# Infinity_Mirror_005.net
KiCad netlist of a schematic drawn in EAGLE
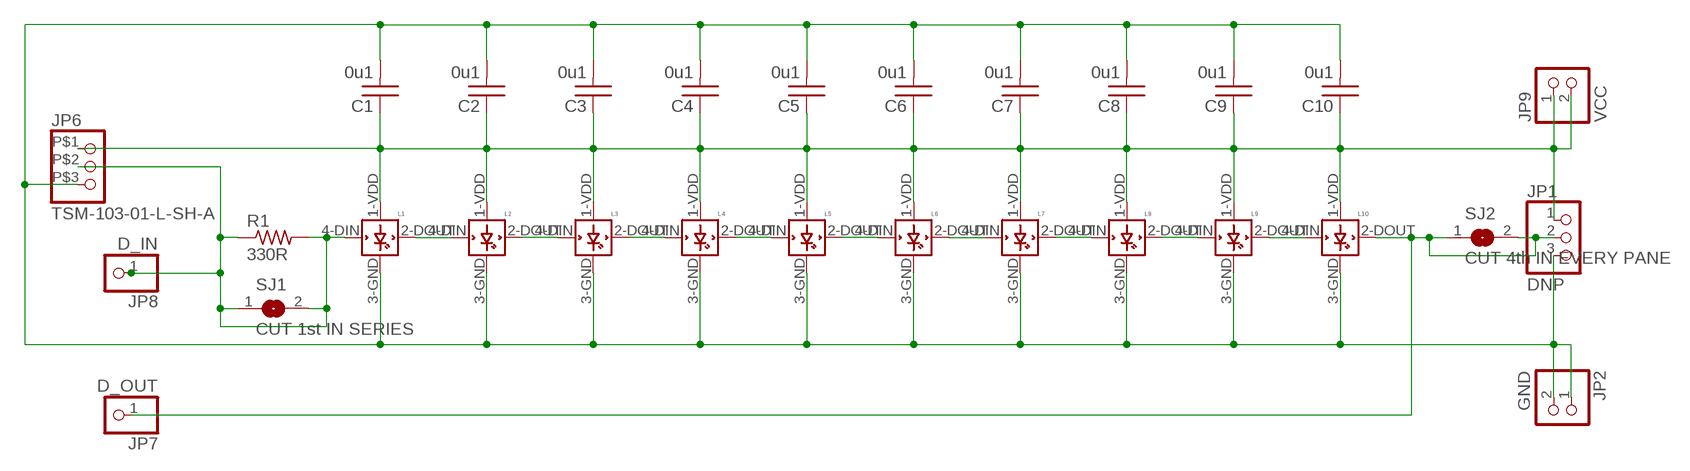
[diagram p0: schematic, sheet 1]

(export (version "E")
  (design (tool "Eeschema 10.0.6"))
  (components
    (comp (ref "C1")
      (value "0u1")
      (footprint "eagle-import:C1206")
      (libsource (lib "eagle-import") (part "C-USC1206"))
    )
    (comp (ref "C2")
      (value "0u1")
      (footprint "eagle-import:C1206")
      (libsource (lib "eagle-import") (part "C-USC1206"))
    )
    (comp (ref "C3")
      (value "0u1")
      (footprint "eagle-import:C1206")
      (libsource (lib "eagle-import") (part "C-USC1206"))
    )
    (comp (ref "C4")
      (value "0u1")
      (footprint "eagle-import:C1206")
      (libsource (lib "eagle-import") (part "C-USC1206"))
    )
    (comp (ref "C5")
      (value "0u1")
      (footprint "eagle-import:C1206")
      (libsource (lib "eagle-import") (part "C-USC1206"))
    )
    (comp (ref "C6")
      (value "0u1")
      (footprint "eagle-import:C1206")
      (libsource (lib "eagle-import") (part "C-USC1206"))
    )
    (comp (ref "C7")
      (value "0u1")
      (footprint "eagle-import:C1206")
      (libsource (lib "eagle-import") (part "C-USC1206"))
    )
    (comp (ref "C8")
      (value "0u1")
      (footprint "eagle-import:C1206")
      (libsource (lib "eagle-import") (part "C-USC1206"))
    )
    (comp (ref "C9")
      (value "0u1")
      (footprint "eagle-import:C1206")
      (libsource (lib "eagle-import") (part "C-USC1206"))
    )
    (comp (ref "C10")
      (value "0u1")
      (footprint "eagle-import:C1206")
      (libsource (lib "eagle-import") (part "C-USC1206"))
    )
    (comp (ref "JP1")
      (value "DNP")
      (footprint "eagle-import:1X03-CLEANBIG")
      (libsource (lib "eagle-import") (part "PINHD-1X3CB"))
    )
    (comp (ref "JP2")
      (value "GND")
      (footprint "eagle-import:1X02-CLEANBIG")
      (libsource (lib "eagle-import") (part "PINHD-1X2"))
    )
    (comp (ref "JP6")
      (value "TSM-103-01-L-SH-A")
      (footprint "eagle-import:TSM-103-01-L-SH-A")
      (libsource (lib "eagle-import") (part "TSM-103-01-L-SH-A"))
    )
    (comp (ref "JP7")
      (value "D_OUT")
      (footprint "eagle-import:1X01-CLEANBIG")
      (libsource (lib "eagle-import") (part "PINHD-1X1CB"))
    )
    (comp (ref "JP8")
      (value "D_IN")
      (footprint "eagle-import:1X01-CLEANBIG")
      (libsource (lib "eagle-import") (part "PINHD-1X1CB"))
    )
    (comp (ref "JP9")
      (value "VCC")
      (footprint "eagle-import:1X02-CLEANBIG")
      (libsource (lib "eagle-import") (part "PINHD-1X2"))
    )
    (comp (ref "L1")
      (value "WS2812B")
      (footprint "eagle-import:WS2812B")
      (libsource (lib "eagle-import") (part "WS2812B"))
    )
    (comp (ref "L2")
      (value "WS2812B")
      (footprint "eagle-import:WS2812B")
      (libsource (lib "eagle-import") (part "WS2812B"))
    )
    (comp (ref "L3")
      (value "WS2812B")
      (footprint "eagle-import:WS2812B")
      (libsource (lib "eagle-import") (part "WS2812B"))
    )
    (comp (ref "L4")
      (value "WS2812B")
      (footprint "eagle-import:WS2812B")
      (libsource (lib "eagle-import") (part "WS2812B"))
    )
    (comp (ref "L5")
      (value "WS2812B")
      (footprint "eagle-import:WS2812B")
      (libsource (lib "eagle-import") (part "WS2812B"))
    )
    (comp (ref "L6")
      (value "WS2812B")
      (footprint "eagle-import:WS2812B")
      (libsource (lib "eagle-import") (part "WS2812B"))
    )
    (comp (ref "L7")
      (value "WS2812B")
      (footprint "eagle-import:WS2812B")
      (libsource (lib "eagle-import") (part "WS2812B"))
    )
    (comp (ref "L8")
      (value "WS2812B")
      (footprint "eagle-import:WS2812B")
      (libsource (lib "eagle-import") (part "WS2812B"))
    )
    (comp (ref "L9")
      (value "WS2812B")
      (footprint "eagle-import:WS2812B")
      (libsource (lib "eagle-import") (part "WS2812B"))
    )
    (comp (ref "L10")
      (value "WS2812B")
      (footprint "eagle-import:WS2812B")
      (libsource (lib "eagle-import") (part "WS2812B"))
    )
    (comp (ref "R1")
      (value "330R")
      (footprint "eagle-import:R1206")
      (libsource (lib "eagle-import") (part "R-US_R1206"))
    )
    (comp (ref "SJ1")
      (value "CUT 1st IN SERIES")
      (footprint "eagle-import:SJ")
      (libsource (lib "eagle-import") (part "SJ"))
    )
    (comp (ref "SJ2")
      (value "CUT 4th IN EVERY PANE")
      (footprint "eagle-import:SJ")
      (libsource (lib "eagle-import") (part "SJ"))
    )
  )
  (nets
    (net (code "1") (name "Net-(JP6-1)") (class "Default")
      (node (ref "C1") (pin "1") (pinfunction "1_1") (pintype "passive"))
      (node (ref "C10") (pin "1") (pinfunction "1_1") (pintype "passive"))
      (node (ref "C2") (pin "1") (pinfunction "1_1") (pintype "passive"))
      (node (ref "C3") (pin "1") (pinfunction "1_1") (pintype "passive"))
      (node (ref "C4") (pin "1") (pinfunction "1_1") (pintype "passive"))
      (node (ref "C5") (pin "1") (pinfunction "1_1") (pintype "passive"))
      (node (ref "C6") (pin "1") (pinfunction "1_1") (pintype "passive"))
      (node (ref "C7") (pin "1") (pinfunction "1_1") (pintype "passive"))
      (node (ref "C8") (pin "1") (pinfunction "1_1") (pintype "passive"))
      (node (ref "C9") (pin "1") (pinfunction "1_1") (pintype "passive"))
      (node (ref "JP1") (pin "1") (pinfunction "1_1") (pintype "passive"))
      (node (ref "JP6") (pin "P$1") (pinfunction "1_P$1") (pintype "passive"))
      (node (ref "JP9") (pin "1") (pinfunction "1_1") (pintype "passive"))
      (node (ref "JP9") (pin "2") (pinfunction "2_2") (pintype "passive"))
      (node (ref "L1") (pin "1-VDD") (pinfunction "VDD_1-VDD") (pintype "bidirectional"))
      (node (ref "L10") (pin "1-VDD") (pinfunction "VDD_1-VDD") (pintype "bidirectional"))
      (node (ref "L2") (pin "1-VDD") (pinfunction "VDD_1-VDD") (pintype "bidirectional"))
      (node (ref "L3") (pin "1-VDD") (pinfunction "VDD_1-VDD") (pintype "bidirectional"))
      (node (ref "L4") (pin "1-VDD") (pinfunction "VDD_1-VDD") (pintype "bidirectional"))
      (node (ref "L5") (pin "1-VDD") (pinfunction "VDD_1-VDD") (pintype "bidirectional"))
      (node (ref "L6") (pin "1-VDD") (pinfunction "VDD_1-VDD") (pintype "bidirectional"))
      (node (ref "L7") (pin "1-VDD") (pinfunction "VDD_1-VDD") (pintype "bidirectional"))
      (node (ref "L8") (pin "1-VDD") (pinfunction "VDD_1-VDD") (pintype "bidirectional"))
      (node (ref "L9") (pin "1-VDD") (pinfunction "VDD_1-VDD") (pintype "bidirectional"))
    )
    (net (code "2") (name "Net-(JP6-2)") (class "Default")
      (node (ref "JP6") (pin "P$2") (pinfunction "2_P$2") (pintype "passive"))
      (node (ref "JP8") (pin "1") (pinfunction "1_1") (pintype "passive"))
      (node (ref "L1") (pin "4-DIN") (pinfunction "DIN_4-DIN") (pintype "input"))
      (node (ref "R1") (pin "1") (pinfunction "1_1") (pintype "passive"))
      (node (ref "R1") (pin "2") (pinfunction "2_2") (pintype "passive"))
      (node (ref "SJ1") (pin "1") (pinfunction "1_1") (pintype "passive"))
      (node (ref "SJ1") (pin "2") (pinfunction "2_2") (pintype "passive"))
    )
    (net (code "3") (name "Net-(JP6-3)") (class "Default")
      (node (ref "C1") (pin "2") (pinfunction "2_2") (pintype "passive"))
      (node (ref "C10") (pin "2") (pinfunction "2_2") (pintype "passive"))
      (node (ref "C2") (pin "2") (pinfunction "2_2") (pintype "passive"))
      (node (ref "C3") (pin "2") (pinfunction "2_2") (pintype "passive"))
      (node (ref "C4") (pin "2") (pinfunction "2_2") (pintype "passive"))
      (node (ref "C5") (pin "2") (pinfunction "2_2") (pintype "passive"))
      (node (ref "C6") (pin "2") (pinfunction "2_2") (pintype "passive"))
      (node (ref "C7") (pin "2") (pinfunction "2_2") (pintype "passive"))
      (node (ref "C8") (pin "2") (pinfunction "2_2") (pintype "passive"))
      (node (ref "C9") (pin "2") (pinfunction "2_2") (pintype "passive"))
      (node (ref "JP1") (pin "3") (pinfunction "3_3") (pintype "passive"))
      (node (ref "JP2") (pin "1") (pinfunction "1_1") (pintype "passive"))
      (node (ref "JP2") (pin "2") (pinfunction "2_2") (pintype "passive"))
      (node (ref "JP6") (pin "P$3") (pinfunction "3_P$3") (pintype "passive"))
      (node (ref "L1") (pin "3-GND") (pinfunction "GND_3-GND") (pintype "bidirectional"))
      (node (ref "L10") (pin "3-GND") (pinfunction "GND_3-GND") (pintype "bidirectional"))
      (node (ref "L2") (pin "3-GND") (pinfunction "GND_3-GND") (pintype "bidirectional"))
      (node (ref "L3") (pin "3-GND") (pinfunction "GND_3-GND") (pintype "bidirectional"))
      (node (ref "L4") (pin "3-GND") (pinfunction "GND_3-GND") (pintype "bidirectional"))
      (node (ref "L5") (pin "3-GND") (pinfunction "GND_3-GND") (pintype "bidirectional"))
      (node (ref "L6") (pin "3-GND") (pinfunction "GND_3-GND") (pintype "bidirectional"))
      (node (ref "L7") (pin "3-GND") (pinfunction "GND_3-GND") (pintype "bidirectional"))
      (node (ref "L8") (pin "3-GND") (pinfunction "GND_3-GND") (pintype "bidirectional"))
      (node (ref "L9") (pin "3-GND") (pinfunction "GND_3-GND") (pintype "bidirectional"))
    )
    (net (code "4") (name "Net-(L1-DOUT)") (class "Default")
      (node (ref "L1") (pin "2-DOUT") (pinfunction "DOUT_2-DOUT") (pintype "output"))
      (node (ref "L2") (pin "4-DIN") (pinfunction "DIN_4-DIN") (pintype "input"))
    )
    (net (code "5") (name "Net-(L2-DOUT)") (class "Default")
      (node (ref "L2") (pin "2-DOUT") (pinfunction "DOUT_2-DOUT") (pintype "output"))
      (node (ref "L3") (pin "4-DIN") (pinfunction "DIN_4-DIN") (pintype "input"))
    )
    (net (code "6") (name "Net-(L3-DOUT)") (class "Default")
      (node (ref "L3") (pin "2-DOUT") (pinfunction "DOUT_2-DOUT") (pintype "output"))
      (node (ref "L4") (pin "4-DIN") (pinfunction "DIN_4-DIN") (pintype "input"))
    )
    (net (code "7") (name "Net-(L4-DOUT)") (class "Default")
      (node (ref "L4") (pin "2-DOUT") (pinfunction "DOUT_2-DOUT") (pintype "output"))
      (node (ref "L5") (pin "4-DIN") (pinfunction "DIN_4-DIN") (pintype "input"))
    )
    (net (code "8") (name "Net-(L5-DOUT)") (class "Default")
      (node (ref "L5") (pin "2-DOUT") (pinfunction "DOUT_2-DOUT") (pintype "output"))
      (node (ref "L6") (pin "4-DIN") (pinfunction "DIN_4-DIN") (pintype "input"))
    )
    (net (code "9") (name "Net-(L6-DOUT)") (class "Default")
      (node (ref "L6") (pin "2-DOUT") (pinfunction "DOUT_2-DOUT") (pintype "output"))
      (node (ref "L7") (pin "4-DIN") (pinfunction "DIN_4-DIN") (pintype "input"))
    )
    (net (code "10") (name "Net-(L7-DOUT)") (class "Default")
      (node (ref "L7") (pin "2-DOUT") (pinfunction "DOUT_2-DOUT") (pintype "output"))
      (node (ref "L8") (pin "4-DIN") (pinfunction "DIN_4-DIN") (pintype "input"))
    )
    (net (code "11") (name "Net-(L8-DOUT)") (class "Default")
      (node (ref "L8") (pin "2-DOUT") (pinfunction "DOUT_2-DOUT") (pintype "output"))
      (node (ref "L9") (pin "4-DIN") (pinfunction "DIN_4-DIN") (pintype "input"))
    )
    (net (code "12") (name "Net-(L10-DIN)") (class "Default")
      (node (ref "L10") (pin "4-DIN") (pinfunction "DIN_4-DIN") (pintype "input"))
      (node (ref "L9") (pin "2-DOUT") (pinfunction "DOUT_2-DOUT") (pintype "output"))
    )
    (net (code "13") (name "Net-(L10-DOUT)") (class "Default")
      (node (ref "JP1") (pin "2") (pinfunction "2_2") (pintype "passive"))
      (node (ref "JP7") (pin "1") (pinfunction "1_1") (pintype "passive"))
      (node (ref "L10") (pin "2-DOUT") (pinfunction "DOUT_2-DOUT") (pintype "output"))
      (node (ref "SJ2") (pin "1") (pinfunction "1_1") (pintype "passive"))
      (node (ref "SJ2") (pin "2") (pinfunction "2_2") (pintype "passive"))
    )
  )
)
